# Servo.net
KiCad netlist of a schematic drawn in EAGLE
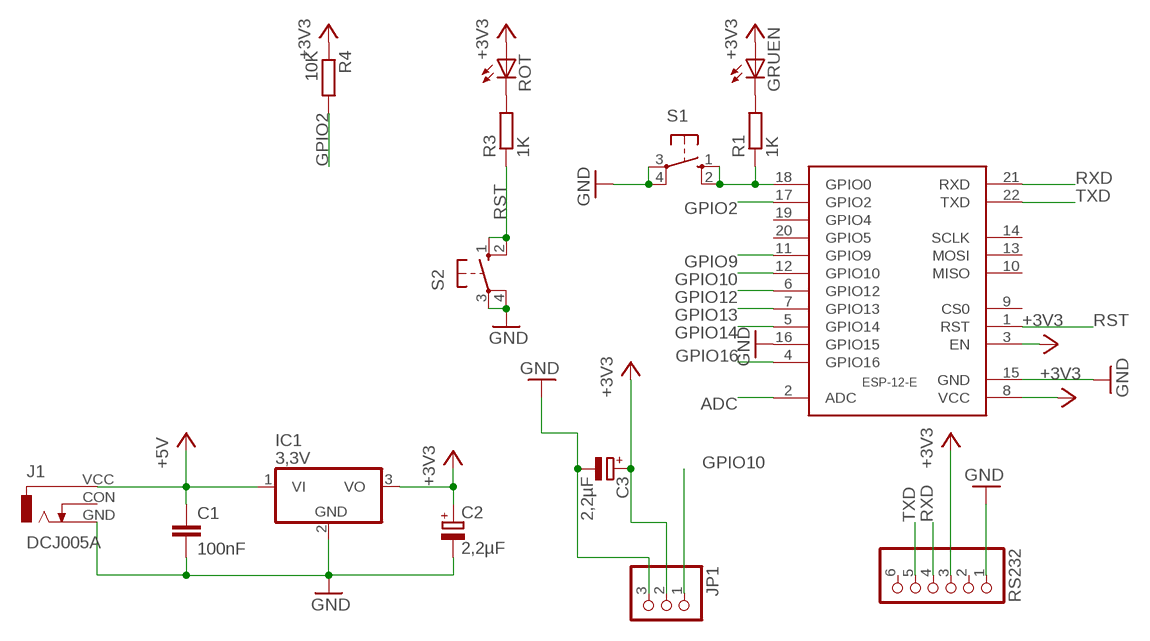
[diagram p0: schematic, sheet 1]

(export (version "E")
  (design (tool "Eeschema 10.0.6"))
  (components
    (comp (ref "C1")
      (value "100nF")
      (footprint "eagle-import:C050-030X075")
      (libsource (lib "eagle-import") (part "C-EU050-030X075"))
    )
    (comp (ref "C2")
      (value "2,2µF")
      (footprint "eagle-import:E2,5-6")
      (libsource (lib "eagle-import") (part "CPOL-EUE2.5-6"))
    )
    (comp (ref "C3")
      (value "2,2µF")
      (footprint "eagle-import:E2,5-6")
      (libsource (lib "eagle-import") (part "CPOL-EUE2.5-6"))
    )
    (comp (ref "GRUEN")
      (value "LED5MM")
      (footprint "eagle-import:LED5MM")
      (libsource (lib "eagle-import") (part "LED5MM"))
    )
    (comp (ref "IC1")
      (value "3,3V")
      (footprint "eagle-import:TO220V")
      (libsource (lib "eagle-import") (part "78TV05"))
    )
    (comp (ref "J1")
      (value "DCJ005A")
      (footprint "eagle-import:DC005A")
      (libsource (lib "eagle-import") (part "DCJ005A"))
    )
    (comp (ref "JP1")
      (value "PINHD-1X3")
      (footprint "eagle-import:1X03")
      (libsource (lib "eagle-import") (part "PINHD-1X3"))
    )
    (comp (ref "R1")
      (value "1K")
      (footprint "eagle-import:0207_10")
      (libsource (lib "eagle-import") (part "R-EU_0207/10"))
    )
    (comp (ref "R3")
      (value "1K")
      (footprint "eagle-import:0207_10")
      (libsource (lib "eagle-import") (part "R-EU_0207/10"))
    )
    (comp (ref "R4")
      (value "10K")
      (footprint "eagle-import:0207_10")
      (libsource (lib "eagle-import") (part "R-EU_0207/10"))
    )
    (comp (ref "ROT")
      (value "LED5MM")
      (footprint "eagle-import:LED5MM")
      (libsource (lib "eagle-import") (part "LED5MM"))
    )
    (comp (ref "RS232")
      (value "PINHD-1X6")
      (footprint "eagle-import:1X06")
      (libsource (lib "eagle-import") (part "PINHD-1X6"))
    )
    (comp (ref "S1")
      (value "10-XX")
      (footprint "eagle-import:B3F-10XX")
      (fields (field (name "MPN") "B3F-1000"))
      (libsource (lib "eagle-import") (part "10-XX"))
    )
    (comp (ref "S2")
      (value "10-XX")
      (footprint "eagle-import:B3F-10XX")
      (fields (field (name "MPN") "B3F-1000"))
      (libsource (lib "eagle-import") (part "10-XX"))
    )
    (comp (ref "U$1")
      (value "ESP-12-E")
      (footprint "eagle-import:ESP-12-E")
      (libsource (lib "eagle-import") (part "ESP-12-E"))
    )
  )
  (nets
    (net (code "1") (name "+3V3") (class "Default")
      (node (ref "C2") (pin "+") (pinfunction "+_+") (pintype "passive"))
      (node (ref "C3") (pin "+") (pinfunction "+_+") (pintype "passive"))
      (node (ref "GRUEN") (pin "A") (pinfunction "A_A") (pintype "passive"))
      (node (ref "IC1") (pin "3") (pinfunction "VO_3") (pintype "passive"))
      (node (ref "JP1") (pin "2") (pinfunction "2_2") (pintype "passive"))
      (node (ref "R4") (pin "1") (pinfunction "1_1") (pintype "passive"))
      (node (ref "ROT") (pin "A") (pinfunction "A_A") (pintype "passive"))
      (node (ref "RS232") (pin "3") (pinfunction "3_3") (pintype "passive"))
      (node (ref "U$1") (pin "3") (pinfunction "EN_3") (pintype "bidirectional"))
      (node (ref "U$1") (pin "8") (pinfunction "VCC_8") (pintype "power_in"))
    )
    (net (code "2") (name "+5V") (class "Default")
      (node (ref "C1") (pin "1") (pinfunction "1_1") (pintype "passive"))
      (node (ref "IC1") (pin "1") (pinfunction "VI_1") (pintype "input"))
      (node (ref "J1") (pin "VCC") (pinfunction "1_VCC") (pintype "passive"))
    )
    (net (code "3") (name "/ADC") (class "Default")
      (node (ref "U$1") (pin "2") (pinfunction "ADC_2") (pintype "bidirectional"))
    )
    (net (code "4") (name "/GPIO2") (class "Default")
      (node (ref "R4") (pin "2") (pinfunction "2_2") (pintype "passive"))
      (node (ref "U$1") (pin "17") (pinfunction "GPIO2_17") (pintype "bidirectional"))
    )
    (net (code "5") (name "/GPIO9") (class "Default")
      (node (ref "U$1") (pin "11") (pinfunction "GPIO9_11") (pintype "bidirectional"))
    )
    (net (code "6") (name "/GPIO10") (class "Default")
      (node (ref "JP1") (pin "1") (pinfunction "1_1") (pintype "passive"))
      (node (ref "U$1") (pin "12") (pinfunction "GPIO10_12") (pintype "bidirectional"))
    )
    (net (code "7") (name "/GPIO12") (class "Default")
      (node (ref "U$1") (pin "6") (pinfunction "GPIO12_6") (pintype "bidirectional"))
    )
    (net (code "8") (name "/GPIO13") (class "Default")
      (node (ref "U$1") (pin "7") (pinfunction "GPIO13_7") (pintype "bidirectional"))
    )
    (net (code "9") (name "/GPIO14") (class "Default")
      (node (ref "U$1") (pin "5") (pinfunction "GPIO14_5") (pintype "bidirectional"))
    )
    (net (code "10") (name "/GPIO16") (class "Default")
      (node (ref "U$1") (pin "4") (pinfunction "GPIO16_4") (pintype "bidirectional"))
    )
    (net (code "11") (name "/RST") (class "Default")
      (node (ref "R3") (pin "1") (pinfunction "1_1") (pintype "passive"))
      (node (ref "S2") (pin "1") (pinfunction "S_1") (pintype "passive"))
      (node (ref "S2") (pin "2") (pinfunction "S1_2") (pintype "passive"))
      (node (ref "U$1") (pin "1") (pinfunction "RST_1") (pintype "bidirectional"))
    )
    (net (code "12") (name "/RXD") (class "Default")
      (node (ref "RS232") (pin "4") (pinfunction "4_4") (pintype "passive"))
      (node (ref "U$1") (pin "21") (pinfunction "RXD_21") (pintype "bidirectional"))
    )
    (net (code "13") (name "/TXD") (class "Default")
      (node (ref "RS232") (pin "5") (pinfunction "5_5") (pintype "passive"))
      (node (ref "U$1") (pin "22") (pinfunction "TXD_22") (pintype "bidirectional"))
    )
    (net (code "14") (name "GND") (class "Default")
      (node (ref "C1") (pin "2") (pinfunction "2_2") (pintype "passive"))
      (node (ref "C2") (pin "-") (pinfunction "-_-") (pintype "passive"))
      (node (ref "C3") (pin "-") (pinfunction "-_-") (pintype "passive"))
      (node (ref "IC1") (pin "2") (pinfunction "GND_2") (pintype "passive"))
      (node (ref "J1") (pin "GND") (pinfunction "3_GND") (pintype "passive"))
      (node (ref "JP1") (pin "3") (pinfunction "3_3") (pintype "passive"))
      (node (ref "RS232") (pin "1") (pinfunction "1_1") (pintype "passive"))
      (node (ref "S1") (pin "3") (pinfunction "P_3") (pintype "passive"))
      (node (ref "S1") (pin "4") (pinfunction "P1_4") (pintype "passive"))
      (node (ref "S2") (pin "3") (pinfunction "P_3") (pintype "passive"))
      (node (ref "S2") (pin "4") (pinfunction "P1_4") (pintype "passive"))
      (node (ref "U$1") (pin "15") (pinfunction "GND_15") (pintype "power_in"))
      (node (ref "U$1") (pin "16") (pinfunction "GPIO15_16") (pintype "bidirectional"))
    )
    (net (code "15") (name "Net-(GRUEN-C)") (class "Default")
      (node (ref "GRUEN") (pin "K") (pinfunction "C_K") (pintype "passive"))
      (node (ref "R1") (pin "2") (pinfunction "2_2") (pintype "passive"))
    )
    (net (code "16") (name "Net-(ROT-C)") (class "Default")
      (node (ref "R3") (pin "2") (pinfunction "2_2") (pintype "passive"))
      (node (ref "ROT") (pin "K") (pinfunction "C_K") (pintype "passive"))
    )
    (net (code "17") (name "Net-(S1-S)") (class "Default")
      (node (ref "R1") (pin "1") (pinfunction "1_1") (pintype "passive"))
      (node (ref "S1") (pin "1") (pinfunction "S_1") (pintype "passive"))
      (node (ref "S1") (pin "2") (pinfunction "S1_2") (pintype "passive"))
      (node (ref "U$1") (pin "18") (pinfunction "GPIO0_18") (pintype "bidirectional"))
    )
    (net (code "18") (name "unconnected-(J1-2-PadCON)") (class "Default")
      (node (ref "J1") (pin "CON") (pinfunction "2_CON") (pintype "passive"))
    )
    (net (code "19") (name "unconnected-(RS232-Pad2)") (class "Default")
      (node (ref "RS232") (pin "2") (pinfunction "2_2") (pintype "passive"))
    )
    (net (code "20") (name "unconnected-(RS232-Pad6)") (class "Default")
      (node (ref "RS232") (pin "6") (pinfunction "6_6") (pintype "passive"))
    )
    (net (code "21") (name "unconnected-(U$1-CS0-Pad9)") (class "Default")
      (node (ref "U$1") (pin "9") (pinfunction "CS0_9") (pintype "bidirectional"))
    )
    (net (code "22") (name "unconnected-(U$1-GPIO4-Pad19)") (class "Default")
      (node (ref "U$1") (pin "19") (pinfunction "GPIO4_19") (pintype "bidirectional"))
    )
    (net (code "23") (name "unconnected-(U$1-GPIO5-Pad20)") (class "Default")
      (node (ref "U$1") (pin "20") (pinfunction "GPIO5_20") (pintype "bidirectional"))
    )
    (net (code "24") (name "unconnected-(U$1-MISO-Pad10)") (class "Default")
      (node (ref "U$1") (pin "10") (pinfunction "MISO_10") (pintype "bidirectional"))
    )
    (net (code "25") (name "unconnected-(U$1-MOSI-Pad13)") (class "Default")
      (node (ref "U$1") (pin "13") (pinfunction "MOSI_13") (pintype "bidirectional"))
    )
    (net (code "26") (name "unconnected-(U$1-SCLK-Pad14)") (class "Default")
      (node (ref "U$1") (pin "14") (pinfunction "SCLK_14") (pintype "bidirectional"))
    )
  )
)
